# main.net
KiCad netlist of a schematic drawn in Altium Designer
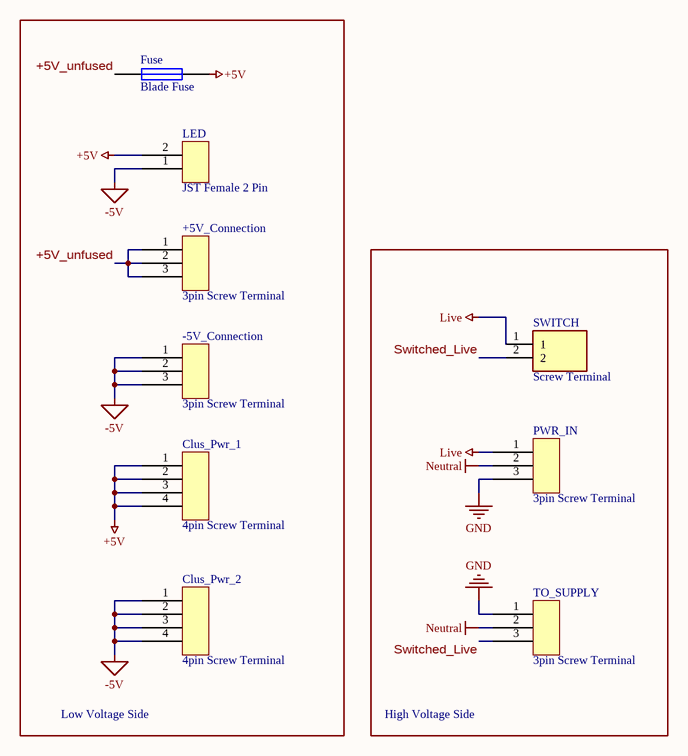
[diagram p0: main.SchDoc]

(export (version "E")
  (design (tool "Eeschema 10.0.6"))
  (components
    (comp (ref "+5V_Connection")
      (value "3pin Screw Terminal")
      (footprint "3pin Screw Terminal")
      (libsource (lib "Misc Components") (part "3pin Screw Terminal"))
    )
    (comp (ref "-5V_Connection")
      (value "3pin Screw Terminal")
      (footprint "3pin Screw Terminal")
      (libsource (lib "Misc Components") (part "3pin Screw Terminal"))
    )
    (comp (ref "Clus_Pwr_1")
      (value "4pin Screw Terminal")
      (footprint "4pin Screw Terminal")
      (libsource (lib "Misc Components") (part "4pin Screw Terminal"))
    )
    (comp (ref "Clus_Pwr_2")
      (value "4pin Screw Terminal")
      (footprint "4pin Screw Terminal")
      (libsource (lib "Misc Components") (part "4pin Screw Terminal"))
    )
    (comp (ref "Fuse")
      (value "Blade Fuse")
      (footprint "Blade Fuse [Standard]")
      (description "Standard Fuse Socket")
      (libsource (lib "Misc Components") (part "Blade Fuse"))
    )
    (comp (ref "LED")
      (value "JST Female 2 Pin")
      (footprint "JST FEMALE 2PIN")
      (libsource (lib "Misc Components") (part "JST Female 2 Pin"))
    )
    (comp (ref "PWR_IN")
      (value "3pin Screw Terminal")
      (footprint "3pin Screw Terminal")
      (libsource (lib "Misc Components") (part "3pin Screw Terminal"))
    )
    (comp (ref "SWITCH")
      (value "Screw Terminal")
      (footprint "SamacSys:TB00250002BE")
      (description "Connector")
      (fields
        (field (name "MANUFACTURER_PART_NUMBER") "TB002-500-02BE")
        (field (name "MOUSER PART NUMBER") "490-TB002-500-02BE")
      )
      (libsource (lib "SamacSys") (part "Screw Terminal"))
    )
    (comp (ref "TO_SUPPLY")
      (value "3pin Screw Terminal")
      (footprint "3pin Screw Terminal")
      (libsource (lib "Misc Components") (part "3pin Screw Terminal"))
    )
  )
  (nets
    (net (code "1") (name "+5V") (class "Default")
      (node (ref "Clus_Pwr_1") (pin "1") (pintype "power_in"))
      (node (ref "Clus_Pwr_1") (pin "2") (pintype "power_in"))
      (node (ref "Clus_Pwr_1") (pin "3") (pintype "power_in"))
      (node (ref "Clus_Pwr_1") (pin "4") (pintype "power_in"))
      (node (ref "Fuse") (pin "2") (pinfunction "2_2") (pintype "passive"))
      (node (ref "LED") (pin "2") (pintype "power_in"))
    )
    (net (code "2") (name "-5V") (class "Default")
      (node (ref "-5V_Connection") (pin "1") (pintype "power_in"))
      (node (ref "-5V_Connection") (pin "2") (pintype "power_in"))
      (node (ref "-5V_Connection") (pin "3") (pintype "power_in"))
      (node (ref "Clus_Pwr_2") (pin "1") (pintype "power_in"))
      (node (ref "Clus_Pwr_2") (pin "2") (pintype "power_in"))
      (node (ref "Clus_Pwr_2") (pin "3") (pintype "power_in"))
      (node (ref "Clus_Pwr_2") (pin "4") (pintype "power_in"))
      (node (ref "LED") (pin "1") (pintype "power_in"))
    )
    (net (code "3") (name "/+5V_unfused") (class "Default")
      (node (ref "+5V_Connection") (pin "1") (pintype "power_in"))
      (node (ref "+5V_Connection") (pin "2") (pintype "power_in"))
      (node (ref "+5V_Connection") (pin "3") (pintype "power_in"))
      (node (ref "Fuse") (pin "1") (pinfunction "1_1") (pintype "passive"))
    )
    (net (code "4") (name "/Switched_Live") (class "Default")
      (node (ref "SWITCH") (pin "2") (pinfunction "2_2") (pintype "passive"))
      (node (ref "TO_SUPPLY") (pin "3") (pintype "power_in"))
    )
    (net (code "5") (name "GND") (class "Default")
      (node (ref "PWR_IN") (pin "3") (pintype "power_in"))
      (node (ref "TO_SUPPLY") (pin "1") (pintype "power_in"))
    )
    (net (code "6") (name "Live") (class "Default")
      (node (ref "PWR_IN") (pin "1") (pintype "power_in"))
      (node (ref "SWITCH") (pin "1") (pinfunction "1_1") (pintype "passive"))
    )
    (net (code "7") (name "Neutral") (class "Default")
      (node (ref "PWR_IN") (pin "2") (pintype "power_in"))
      (node (ref "TO_SUPPLY") (pin "2") (pintype "power_in"))
    )
  )
)
